# H1DR20.net
KiCad netlist of a schematic drawn in EAGLE
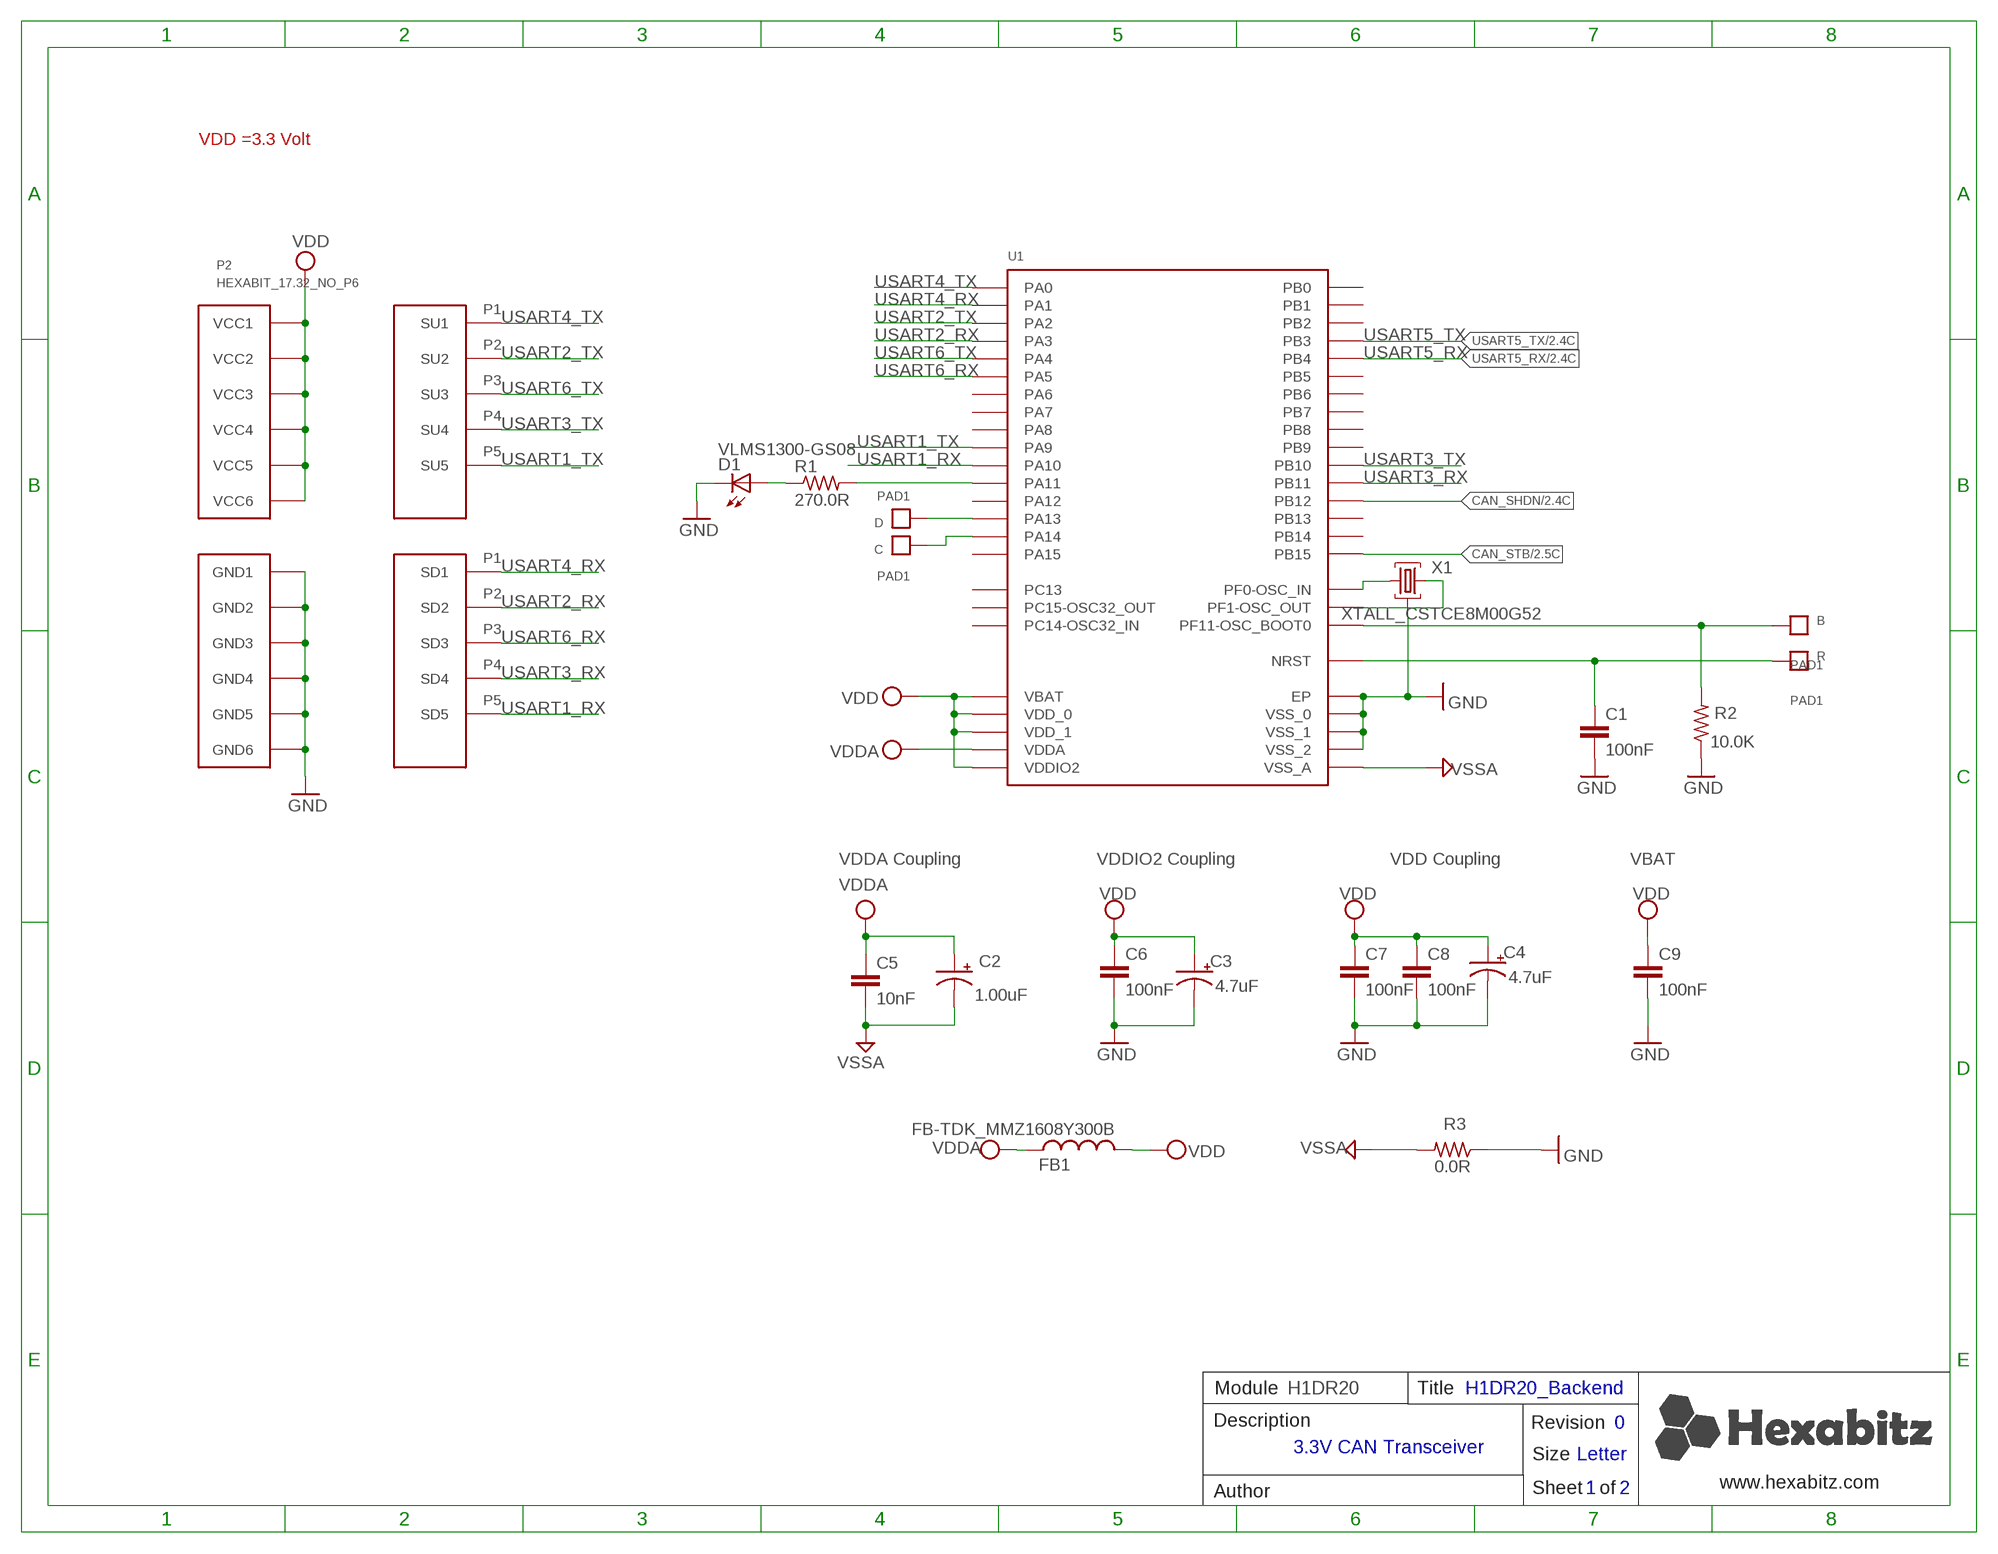
[diagram p0: schematic, sheet 1]
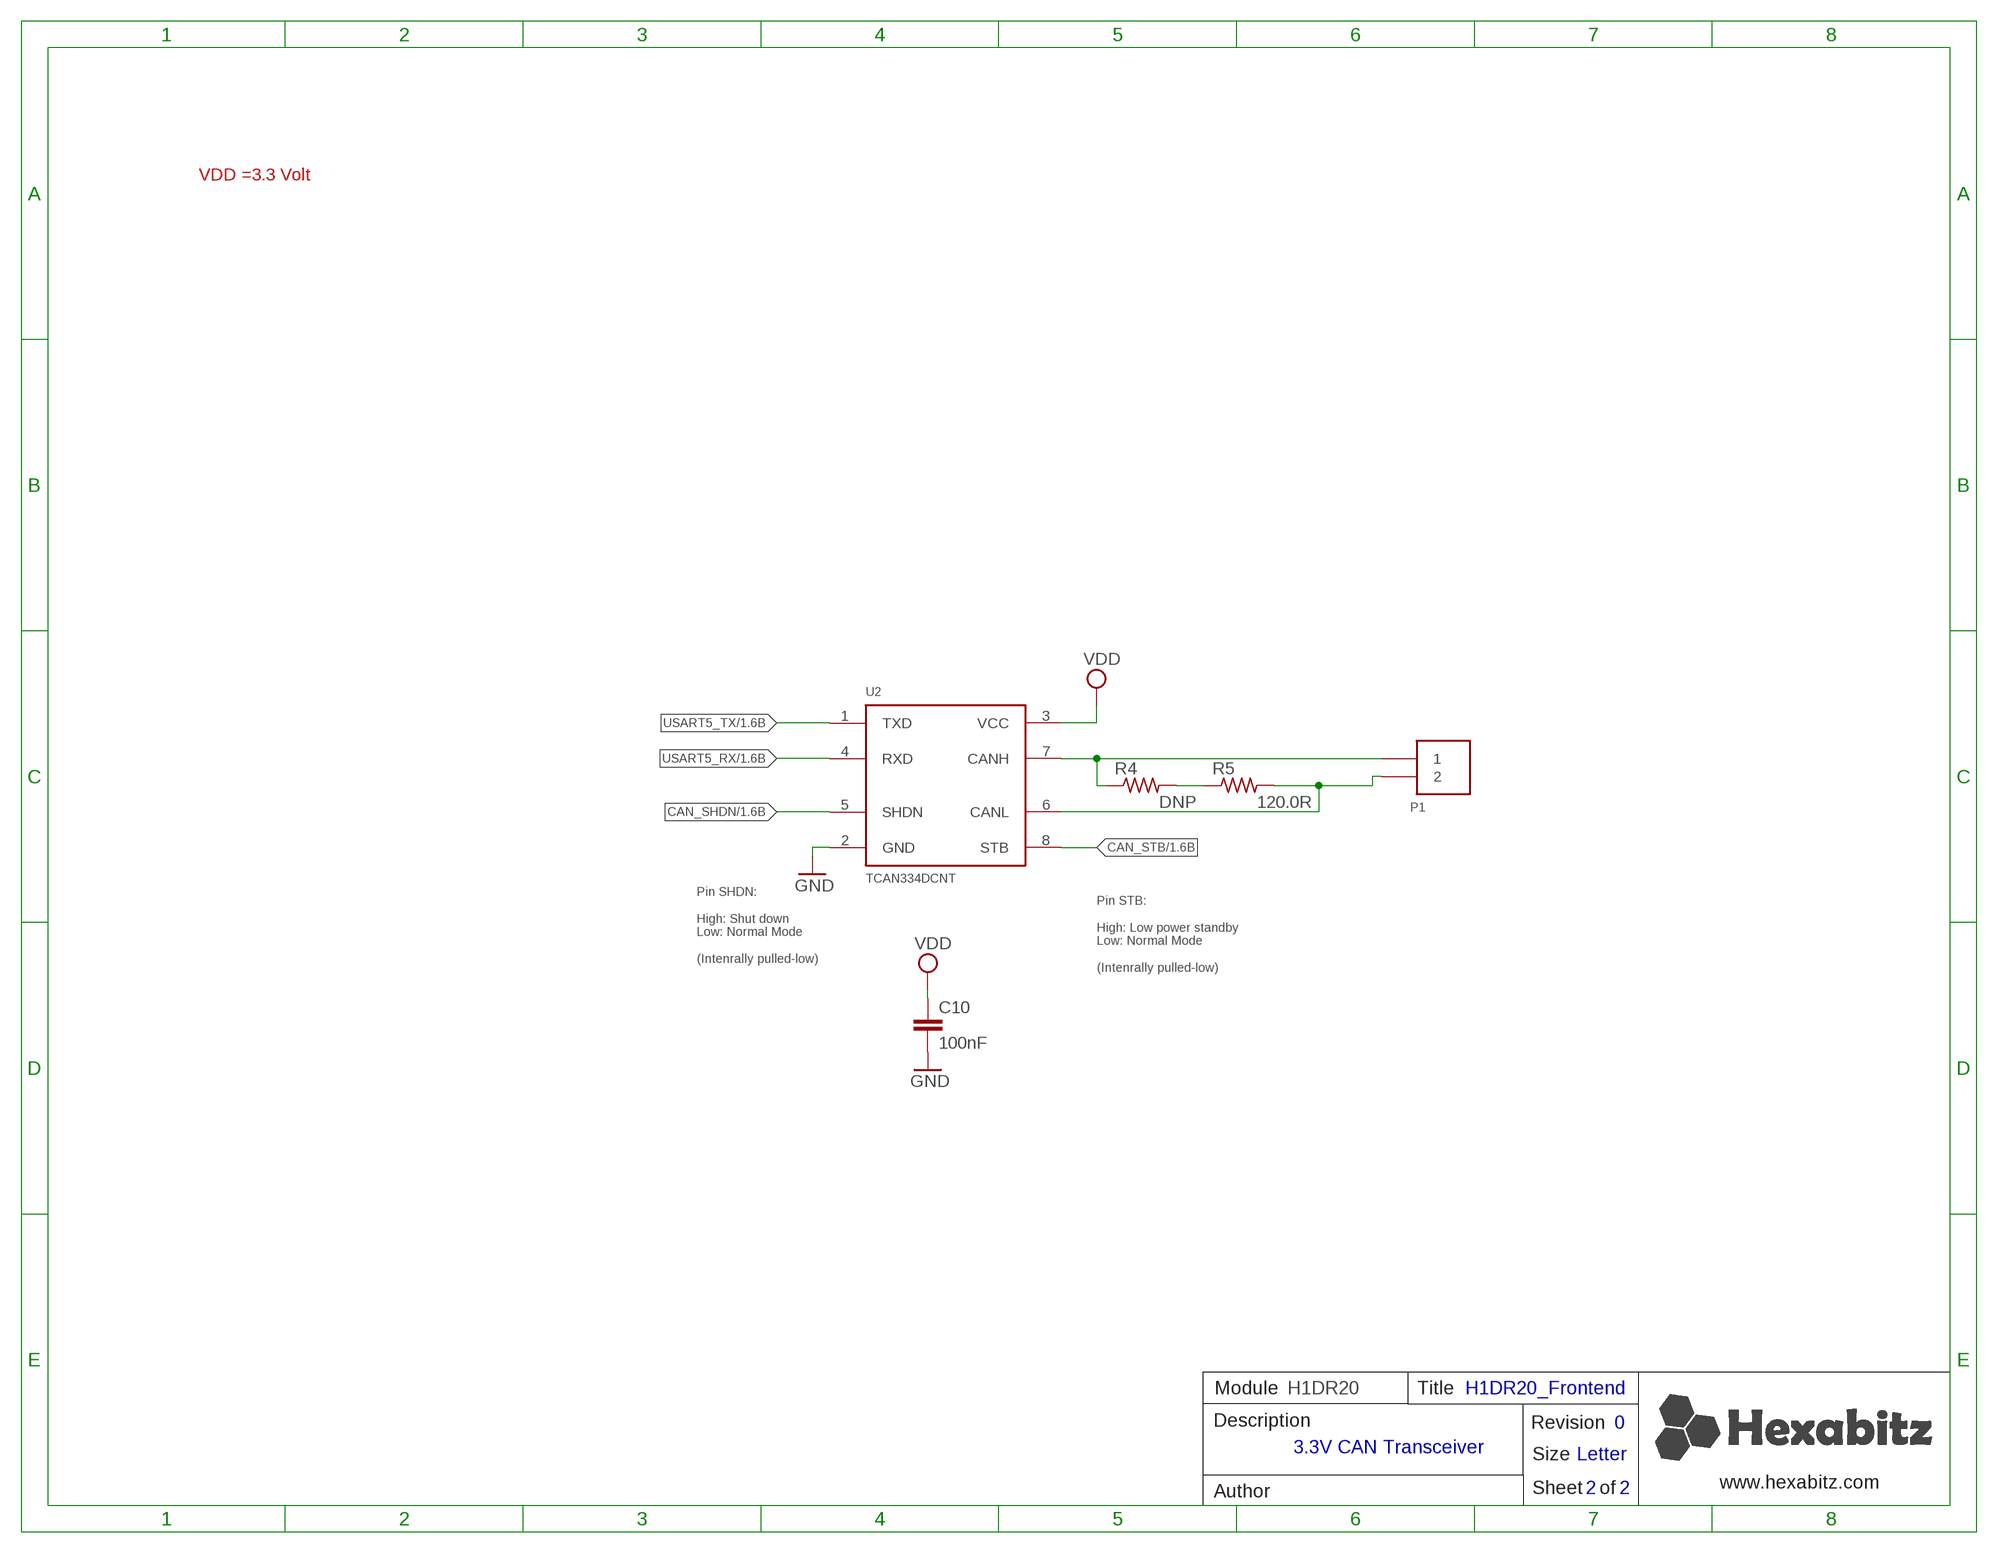
[diagram p1: schematic, sheet 2]

(export (version "E")
  (design (tool "Eeschema 10.0.6"))
  (components
    (comp (ref "B")
      (value "PAD1")
      (footprint "eagle-import:PAD1")
      (libsource (lib "eagle-import") (part "PAD1"))
    )
    (comp (ref "C")
      (value "PAD1")
      (footprint "eagle-import:PAD1")
      (libsource (lib "eagle-import") (part "PAD1"))
    )
    (comp (ref "C1")
      (value "100nF")
      (footprint "eagle-import:C-0603")
      (fields
        (field (name "CAPACITANCE") "100nF")
        (field (name "MFN") "KEMET")
        (field (name "MPN") "C0603C104K8RACTU")
        (field (name "OCTOPART_URL") "https://octopart.com/c0603c104k8ractu-kemet-145075?r=sp&s=9bS9ASSwSEqMCE9KBEQZ0g")
        (field (name "TOLERANCE") "10%")
        (field (name "VOLTAGE_RATING") "10V")
      )
      (libsource (lib "eagle-import") (part "C-0603"))
    )
    (comp (ref "C2")
      (value "1.00uF")
      (footprint "eagle-import:C-0805-POL")
      (fields
        (field (name "CAPACITANCE") "1.00uF")
        (field (name "MFN") "Yageo")
        (field (name "MPN") "CC0805KKX7R7BB105")
        (field (name "OCTOPART_URL") "https://octopart.com/cc0805kkx7r7bb105-yageo-8376555?r=sp&s=YKl1wwtkROau_X5nniH2ig")
        (field (name "TOLERANCE") "10%")
        (field (name "VOLTAGE_RATING") "16V")
      )
      (libsource (lib "eagle-import") (part "C-0805-POL"))
    )
    (comp (ref "C3")
      (value "4.7uF")
      (footprint "eagle-import:C-0805-POL")
      (fields
        (field (name "CAPACITANCE") "4.7uF")
        (field (name "MFN") "Murata")
        (field (name "MPN") "GRM21BC81E475KA12L")
        (field (name "OCTOPART_URL") "https://octopart.com/grm21bc81e475ka12l-murata-10331911?r=sp&s=RY3qZSD8T6mG6TC9CHI5qQ")
        (field (name "TOLERANCE") "10%")
        (field (name "VOLTAGE_RATING") "25V")
      )
      (libsource (lib "eagle-import") (part "C-0805-POL"))
    )
    (comp (ref "C4")
      (value "4.7uF")
      (footprint "eagle-import:C-0805-POL")
      (fields
        (field (name "CAPACITANCE") "4.7uF")
        (field (name "MFN") "Murata")
        (field (name "MPN") "GRM21BC81E475KA12L")
        (field (name "OCTOPART_URL") "https://octopart.com/grm21bc81e475ka12l-murata-10331911?r=sp&s=RY3qZSD8T6mG6TC9CHI5qQ")
        (field (name "TOLERANCE") "10%")
        (field (name "VOLTAGE_RATING") "25V")
      )
      (libsource (lib "eagle-import") (part "C-0805-POL"))
    )
    (comp (ref "C5")
      (value "10nF")
      (footprint "eagle-import:C-0603")
      (fields
        (field (name "CAPACITANCE") "10nF")
        (field (name "MFN") "KEMET")
        (field (name "MPN") "C0603C103K5RACTU")
        (field (name "OCTOPART_URL") "https://octopart.com/c0603c103k5ractu-kemet-133094?r=sp&s=R_iPBxLnSmGqhkU2rIMFpg")
        (field (name "TOLERANCE") "10%")
        (field (name "VOLTAGE_RATING") "50V")
      )
      (libsource (lib "eagle-import") (part "C-0603"))
    )
    (comp (ref "C6")
      (value "100nF")
      (footprint "eagle-import:C-0603")
      (fields
        (field (name "CAPACITANCE") "100nF")
        (field (name "MFN") "KEMET")
        (field (name "MPN") "C0603C104K8RACTU")
        (field (name "OCTOPART_URL") "https://octopart.com/c0603c104k8ractu-kemet-145075?r=sp&s=9bS9ASSwSEqMCE9KBEQZ0g")
        (field (name "TOLERANCE") "10%")
        (field (name "VOLTAGE_RATING") "10V")
      )
      (libsource (lib "eagle-import") (part "C-0603"))
    )
    (comp (ref "C7")
      (value "100nF")
      (footprint "eagle-import:C-0603")
      (fields
        (field (name "CAPACITANCE") "100nF")
        (field (name "MFN") "KEMET")
        (field (name "MPN") "C0603C104K8RACTU")
        (field (name "OCTOPART_URL") "https://octopart.com/c0603c104k8ractu-kemet-145075?r=sp&s=9bS9ASSwSEqMCE9KBEQZ0g")
        (field (name "TOLERANCE") "10%")
        (field (name "VOLTAGE_RATING") "10")
      )
      (libsource (lib "eagle-import") (part "C-0603"))
    )
    (comp (ref "C8")
      (value "100nF")
      (footprint "eagle-import:C-0603")
      (fields
        (field (name "CAPACITANCE") "100nF")
        (field (name "MFN") "KEMET")
        (field (name "MPN") "C0603C104K8RACTU")
        (field (name "OCTOPART_URL") "https://octopart.com/c0603c104k8ractu-kemet-145075?r=sp&s=9bS9ASSwSEqMCE9KBEQZ0g")
        (field (name "TOLERANCE") "10%")
        (field (name "VOLTAGE_RATING") "10V")
      )
      (libsource (lib "eagle-import") (part "C-0603"))
    )
    (comp (ref "C9")
      (value "100nF")
      (footprint "eagle-import:C-0603")
      (fields
        (field (name "CAPACITANCE") "100nF")
        (field (name "MFN") "KEMET")
        (field (name "MPN") "C0603C104K8RACTU")
        (field (name "OCTOPART_URL") "https://octopart.com/c0603c104k8ractu-kemet-145075?r=sp&s=9bS9ASSwSEqMCE9KBEQZ0g")
        (field (name "TOLERANCE") "10V")
        (field (name "VOLTAGE_RATING") "10%")
      )
      (libsource (lib "eagle-import") (part "C-0603"))
    )
    (comp (ref "D")
      (value "PAD1")
      (footprint "eagle-import:PAD1")
      (libsource (lib "eagle-import") (part "PAD1"))
    )
    (comp (ref "D1")
      (value "VLMS1300-GS08")
      (footprint "eagle-import:VLMS1300-GS08")
      (fields
        (field (name "MFN") "Vishay")
        (field (name "MPN") "VLMS1300-GS08")
        (field (name "OCTOPART_URL") "https://octopart.com/vlms1300-gs08-vishay-21709201?r=sp&s=_gcP4_q8T1SC6PJQPTQ9yA")
      )
      (libsource (lib "eagle-import") (part "VLMS1300-GS08"))
    )
    (comp (ref "FB1")
      (value "FB-TDK_MMZ1608Y300B")
      (footprint "eagle-import:FB-TDK_MMZ1608Y300B")
      (fields
        (field (name "MFN") "TDK ")
        (field (name "MPN") "MMZ1608Y300B")
        (field (name "OCTOPART_URL") "https://octopart.com/mmz1608y300b-tdk-368280?r=sp&s=cd9_2ZEqQ9q9UNBuQgHAiA")
      )
      (libsource (lib "eagle-import") (part "FB-TDK_MMZ1608Y300B"))
    )
    (comp (ref "P2")
      (value "HEXABIT_17.32_NO_P6")
      (footprint "eagle-import:HEXABIT_17.32_NO_P6")
      (libsource (lib "eagle-import") (part "HEXABIT_17.32_NO_P6"))
    )
    (comp (ref "R")
      (value "PAD1")
      (footprint "eagle-import:PAD1")
      (libsource (lib "eagle-import") (part "PAD1"))
    )
    (comp (ref "R1")
      (value "270.0R")
      (footprint "eagle-import:R-0603")
      (fields
        (field (name "MFN") "Yageo")
        (field (name "MPN") "RC0603FR-07270RL")
        (field (name "OCTOPART_URL") "https://octopart.com/search?q=RC0603FR-07270RL&start=0")
        (field (name "RESISTANCE") "270.0 Ohm")
        (field (name "TOLERANCE") "1%")
      )
      (libsource (lib "eagle-import") (part "R-0603"))
    )
    (comp (ref "R2")
      (value "10.0K")
      (footprint "eagle-import:R-0603")
      (fields
        (field (name "MFN") "Yageo")
        (field (name "MPN") "RC0603JR-0710KL")
        (field (name "OCTOPART_URL") "https://octopart.com/search?q=RC0603JR-0710KL&start=0")
        (field (name "RESISTANCE") "10.0K Ohm")
        (field (name "TOLERANCE") "5%")
      )
      (libsource (lib "eagle-import") (part "R-0603"))
    )
    (comp (ref "R3")
      (value "0.0R")
      (footprint "eagle-import:R-0603")
      (fields
        (field (name "MFN") "Yageo")
        (field (name "MPN") "RC0603JR-070RL")
        (field (name "OCTOPART_URL") "https://octopart.com/rc0603jr-070rl-yageo-1241539?r=sp&s=X2NteqRjRNWrnx42Y0aliA")
        (field (name "RESISTANCE") "0.0 Ohm")
      )
      (libsource (lib "eagle-import") (part "R-0603"))
    )
    (comp (ref "U1")
      (value "STM32F091CBU6")
      (footprint "eagle-import:STM32F091CBU6")
      (libsource (lib "eagle-import") (part "STM32F091CBU6"))
    )
    (comp (ref "X1")
      (value "XTALL_CSTCE8M00G52")
      (footprint "eagle-import:XTALL_CSTCE8M00G52")
      (fields (field (name "MPN") "CSTCE8M00G52Z-R0"))
      (libsource (lib "eagle-import") (part "XTALL_CSTCE8M00G52"))
    )
    (comp (ref "C10")
      (value "100nF")
      (footprint "eagle-import:C-0603")
      (fields
        (field (name "CAPACITANCE") "100nF")
        (field (name "MFN") "KEMET")
        (field (name "MPN") "C0603C104K8RACTU")
        (field (name "OCTOPART_URL") "https://octopart.com/c0603c104k8ractu-kemet-145075?r=sp&s=9bS9ASSwSEqMCE9KBEQZ0g")
        (field (name "TOLERANCE") "10%")
        (field (name "VOLTAGE_RATING") "10V")
      )
      (libsource (lib "eagle-import") (part "C-0603"))
    )
    (comp (ref "P1")
      (value "1546111-2")
      (footprint "eagle-import:1546111-2")
      (libsource (lib "eagle-import") (part "1546111-2"))
    )
    (comp (ref "R4")
      (value "DNP")
      (footprint "eagle-import:R-0603")
      (fields
        (field (name "MFN") "Yageo")
        (field (name "MPN") "RC0603JR-070RL")
        (field (name "OCTOPART_URL") "https://octopart.com/search?q=RC0603JR-070RL")
        (field (name "RESISTANCE") "0.0 Ohm")
      )
      (libsource (lib "eagle-import") (part "R-0603"))
    )
    (comp (ref "R5")
      (value "120.0R")
      (footprint "eagle-import:R-0603")
      (fields
        (field (name "MFN") "Yageo")
        (field (name "MPN") "AC0603FR-07120RL")
        (field (name "OCTOPART_URL") "https://octopart.com/search?q=AC0603FR-07120RL&start=0")
        (field (name "RESISTANCE") "120.0 Ohm")
        (field (name "TOLERANCE") "1%")
      )
      (libsource (lib "eagle-import") (part "R-0603"))
    )
    (comp (ref "U2")
      (value "TCAN334DCNT")
      (footprint "eagle-import:TCAN334DCNT")
      (libsource (lib "eagle-import") (part "TCAN334DCNT"))
    )
  )
  (nets
    (net (code "1") (name "CAN_SHDN") (class "Default")
      (node (ref "U1") (pin "P$25") (pinfunction "PB12_P$25") (pintype "bidirectional"))
      (node (ref "U2") (pin "5") (pinfunction "SHDN_5") (pintype "bidirectional"))
    )
    (net (code "2") (name "CAN_STB") (class "Default")
      (node (ref "U1") (pin "P$28") (pinfunction "PB15_P$28") (pintype "bidirectional"))
      (node (ref "U2") (pin "8") (pinfunction "STB_8") (pintype "bidirectional"))
    )
    (net (code "3") (name "GND") (class "Default")
      (node (ref "C1") (pin "2") (pinfunction "2_2") (pintype "passive"))
      (node (ref "C10") (pin "2") (pinfunction "2_2") (pintype "passive"))
      (node (ref "C3") (pin "2") (pinfunction "-_2") (pintype "passive"))
      (node (ref "C4") (pin "2") (pinfunction "-_2") (pintype "passive"))
      (node (ref "C6") (pin "2") (pinfunction "2_2") (pintype "passive"))
      (node (ref "C7") (pin "2") (pinfunction "2_2") (pintype "passive"))
      (node (ref "C8") (pin "2") (pinfunction "2_2") (pintype "passive"))
      (node (ref "C9") (pin "2") (pinfunction "2_2") (pintype "passive"))
      (node (ref "D1") (pin "C") (pinfunction "C_C") (pintype "passive"))
      (node (ref "P2") (pin "10") (pinfunction "GND4_10") (pintype "power_in"))
      (node (ref "P2") (pin "11") (pinfunction "GND5_11") (pintype "power_in"))
      (node (ref "P2") (pin "12") (pinfunction "GND6_12") (pintype "power_in"))
      (node (ref "P2") (pin "7") (pinfunction "GND1_7") (pintype "power_in"))
      (node (ref "P2") (pin "8") (pinfunction "GND2_8") (pintype "power_in"))
      (node (ref "P2") (pin "9") (pinfunction "GND3_9") (pintype "power_in"))
      (node (ref "R2") (pin "1") (pinfunction "1_1") (pintype "passive"))
      (node (ref "R3") (pin "1") (pinfunction "1_1") (pintype "passive"))
      (node (ref "U1") (pin "EP") (pinfunction "EP_EP") (pintype "power_in"))
      (node (ref "U1") (pin "P$23") (pinfunction "VSS_0_P$23") (pintype "power_in"))
      (node (ref "U1") (pin "P$35") (pinfunction "VSS_1_P$35") (pintype "power_in"))
      (node (ref "U1") (pin "P$47") (pinfunction "VSS_2_P$47") (pintype "power_in"))
      (node (ref "U2") (pin "2") (pinfunction "GND_2") (pintype "bidirectional"))
      (node (ref "X1") (pin "P$2") (pinfunction "2_P$2") (pintype "passive"))
    )
    (net (code "4") (name "Net-(D1-PadA)") (class "Default")
      (node (ref "D1") (pin "A") (pinfunction "A_A") (pintype "passive"))
      (node (ref "R1") (pin "1") (pinfunction "1_1") (pintype "passive"))
    )
    (net (code "5") (name "Net-(R4-Pad2)") (class "Default")
      (node (ref "R4") (pin "2") (pinfunction "2_2") (pintype "passive"))
      (node (ref "R5") (pin "1") (pinfunction "1_1") (pintype "passive"))
    )
    (net (code "6") (name "Net-(U1-NRST)") (class "Default")
      (node (ref "C1") (pin "1") (pinfunction "1_1") (pintype "passive"))
      (node (ref "R") (pin "P$1") (pinfunction "P$1_P$1") (pintype "passive"))
      (node (ref "R") (pin "P$2") (pinfunction "P$1_P$2") (pintype "passive"))
      (node (ref "U1") (pin "P$7") (pinfunction "NRST_P$7") (pintype "passive"))
    )
    (net (code "7") (name "Net-(U1-PA11)") (class "Default")
      (node (ref "R1") (pin "2") (pinfunction "2_2") (pintype "passive"))
      (node (ref "U1") (pin "P$32") (pinfunction "PA11_P$32") (pintype "bidirectional"))
    )
    (net (code "8") (name "Net-(U1-PA13)") (class "Default")
      (node (ref "D") (pin "P$1") (pinfunction "P$1_P$1") (pintype "passive"))
      (node (ref "D") (pin "P$2") (pinfunction "P$1_P$2") (pintype "passive"))
      (node (ref "U1") (pin "P$34") (pinfunction "PA13_P$34") (pintype "bidirectional"))
    )
    (net (code "9") (name "Net-(U1-PA14)") (class "Default")
      (node (ref "C") (pin "P$1") (pinfunction "P$1_P$1") (pintype "passive"))
      (node (ref "C") (pin "P$2") (pinfunction "P$1_P$2") (pintype "passive"))
      (node (ref "U1") (pin "P$37") (pinfunction "PA14_P$37") (pintype "bidirectional"))
    )
    (net (code "10") (name "Net-(U1-PF0-OSC_IN)") (class "Default")
      (node (ref "U1") (pin "P$5") (pinfunction "PF0-OSC_IN_P$5") (pintype "bidirectional"))
      (node (ref "X1") (pin "P$1") (pinfunction "1_P$1") (pintype "passive"))
    )
    (net (code "11") (name "Net-(U1-PF1-OSC_OUT)") (class "Default")
      (node (ref "U1") (pin "P$6") (pinfunction "PF1-OSC_OUT_P$6") (pintype "bidirectional"))
      (node (ref "X1") (pin "P$3") (pinfunction "3_P$3") (pintype "passive"))
    )
    (net (code "12") (name "Net-(U1-PF11-OSC_BOOT0)") (class "Default")
      (node (ref "B") (pin "P$1") (pinfunction "P$1_P$1") (pintype "passive"))
      (node (ref "B") (pin "P$2") (pinfunction "P$1_P$2") (pintype "passive"))
      (node (ref "R2") (pin "2") (pinfunction "2_2") (pintype "passive"))
      (node (ref "U1") (pin "P$44") (pinfunction "PF11-OSC_BOOT0_P$44") (pintype "bidirectional"))
    )
    (net (code "13") (name "Net-(U2-CANH)") (class "Default")
      (node (ref "P1") (pin "1") (pinfunction "1_1") (pintype "power_in"))
      (node (ref "R4") (pin "1") (pinfunction "1_1") (pintype "passive"))
      (node (ref "U2") (pin "7") (pinfunction "CANH_7") (pintype "bidirectional"))
    )
    (net (code "14") (name "Net-(U2-CANL)") (class "Default")
      (node (ref "P1") (pin "2") (pinfunction "2_2") (pintype "power_in"))
      (node (ref "R5") (pin "2") (pinfunction "2_2") (pintype "passive"))
      (node (ref "U2") (pin "6") (pinfunction "CANL_6") (pintype "bidirectional"))
    )
    (net (code "15") (name "USART1_RX") (class "Default")
      (node (ref "P2") (pin "23") (pinfunction "SD5_23") (pintype "bidirectional"))
      (node (ref "U1") (pin "P$31") (pinfunction "PA10_P$31") (pintype "bidirectional"))
    )
    (net (code "16") (name "USART1_TX") (class "Default")
      (node (ref "P2") (pin "17") (pinfunction "SU5_17") (pintype "bidirectional"))
      (node (ref "U1") (pin "P$30") (pinfunction "PA9_P$30") (pintype "bidirectional"))
    )
    (net (code "17") (name "USART2_RX") (class "Default")
      (node (ref "P2") (pin "20") (pinfunction "SD2_20") (pintype "bidirectional"))
      (node (ref "U1") (pin "P$13") (pinfunction "PA3_P$13") (pintype "bidirectional"))
    )
    (net (code "18") (name "USART2_TX") (class "Default")
      (node (ref "P2") (pin "14") (pinfunction "SU2_14") (pintype "bidirectional"))
      (node (ref "U1") (pin "P$12") (pinfunction "PA2_P$12") (pintype "bidirectional"))
    )
    (net (code "19") (name "USART3_RX") (class "Default")
      (node (ref "P2") (pin "22") (pinfunction "SD4_22") (pintype "bidirectional"))
      (node (ref "U1") (pin "P$22") (pinfunction "PB11_P$22") (pintype "bidirectional"))
    )
    (net (code "20") (name "USART3_TX") (class "Default")
      (node (ref "P2") (pin "16") (pinfunction "SU4_16") (pintype "bidirectional"))
      (node (ref "U1") (pin "P$21") (pinfunction "PB10_P$21") (pintype "bidirectional"))
    )
    (net (code "21") (name "USART4_RX") (class "Default")
      (node (ref "P2") (pin "19") (pinfunction "SD1_19") (pintype "bidirectional"))
      (node (ref "U1") (pin "P$11") (pinfunction "PA1_P$11") (pintype "bidirectional"))
    )
    (net (code "22") (name "USART4_TX") (class "Default")
      (node (ref "P2") (pin "13") (pinfunction "SU1_13") (pintype "bidirectional"))
      (node (ref "U1") (pin "P$10") (pinfunction "PA0_P$10") (pintype "bidirectional"))
    )
    (net (code "23") (name "USART5_RX") (class "Default")
      (node (ref "U1") (pin "P$40") (pinfunction "PB4_P$40") (pintype "bidirectional"))
      (node (ref "U2") (pin "4") (pinfunction "RXD_4") (pintype "bidirectional"))
    )
    (net (code "24") (name "USART5_TX") (class "Default")
      (node (ref "U1") (pin "P$39") (pinfunction "PB3_P$39") (pintype "bidirectional"))
      (node (ref "U2") (pin "1") (pinfunction "TXD_1") (pintype "bidirectional"))
    )
    (net (code "25") (name "USART6_RX") (class "Default")
      (node (ref "P2") (pin "21") (pinfunction "SD3_21") (pintype "bidirectional"))
      (node (ref "U1") (pin "P$15") (pinfunction "PA5_P$15") (pintype "bidirectional"))
    )
    (net (code "26") (name "USART6_TX") (class "Default")
      (node (ref "P2") (pin "15") (pinfunction "SU3_15") (pintype "bidirectional"))
      (node (ref "U1") (pin "P$14") (pinfunction "PA4_P$14") (pintype "bidirectional"))
    )
    (net (code "27") (name "VDD") (class "Default")
      (node (ref "C10") (pin "1") (pinfunction "1_1") (pintype "passive"))
      (node (ref "C3") (pin "1") (pinfunction "+_1") (pintype "passive"))
      (node (ref "C4") (pin "1") (pinfunction "+_1") (pintype "passive"))
      (node (ref "C6") (pin "1") (pinfunction "1_1") (pintype "passive"))
      (node (ref "C7") (pin "1") (pinfunction "1_1") (pintype "passive"))
      (node (ref "C8") (pin "1") (pinfunction "1_1") (pintype "passive"))
      (node (ref "C9") (pin "1") (pinfunction "1_1") (pintype "passive"))
      (node (ref "FB1") (pin "2") (pinfunction "2_2") (pintype "passive"))
      (node (ref "P2") (pin "1") (pinfunction "VCC1_1") (pintype "power_in"))
      (node (ref "P2") (pin "2") (pinfunction "VCC2_2") (pintype "power_in"))
      (node (ref "P2") (pin "3") (pinfunction "VCC3_3") (pintype "power_in"))
      (node (ref "P2") (pin "4") (pinfunction "VCC4_4") (pintype "power_in"))
      (node (ref "P2") (pin "5") (pinfunction "VCC5_5") (pintype "power_in"))
      (node (ref "P2") (pin "6") (pinfunction "VCC6_6") (pintype "power_in"))
      (node (ref "U1") (pin "P$1") (pinfunction "VBAT_P$1") (pintype "power_in"))
      (node (ref "U1") (pin "P$24") (pinfunction "VDD_0_P$24") (pintype "power_in"))
      (node (ref "U1") (pin "P$36") (pinfunction "VDDIO2_P$36") (pintype "power_in"))
      (node (ref "U1") (pin "P$48") (pinfunction "VDD_1_P$48") (pintype "power_in"))
      (node (ref "U2") (pin "3") (pinfunction "VCC_3") (pintype "bidirectional"))
    )
    (net (code "28") (name "VDDA") (class "Default")
      (node (ref "C2") (pin "1") (pinfunction "+_1") (pintype "passive"))
      (node (ref "C5") (pin "1") (pinfunction "1_1") (pintype "passive"))
      (node (ref "FB1") (pin "1") (pinfunction "1_1") (pintype "passive"))
      (node (ref "U1") (pin "P$9") (pinfunction "VDDA_P$9") (pintype "power_in"))
    )
    (net (code "29") (name "VSSA") (class "Default")
      (node (ref "C2") (pin "2") (pinfunction "-_2") (pintype "passive"))
      (node (ref "C5") (pin "2") (pinfunction "2_2") (pintype "passive"))
      (node (ref "R3") (pin "2") (pinfunction "2_2") (pintype "passive"))
      (node (ref "U1") (pin "P$8") (pinfunction "VSS_A_P$8") (pintype "power_in"))
    )
    (net (code "30") (name "unconnected-(U1-PA6-PadP$16)") (class "Default")
      (node (ref "U1") (pin "P$16") (pinfunction "PA6_P$16") (pintype "bidirectional"))
    )
    (net (code "31") (name "unconnected-(U1-PA7-PadP$17)") (class "Default")
      (node (ref "U1") (pin "P$17") (pinfunction "PA7_P$17") (pintype "bidirectional"))
    )
    (net (code "32") (name "unconnected-(U1-PA8-PadP$29)") (class "Default")
      (node (ref "U1") (pin "P$29") (pinfunction "PA8_P$29") (pintype "bidirectional"))
    )
    (net (code "33") (name "unconnected-(U1-PA12-PadP$33)") (class "Default")
      (node (ref "U1") (pin "P$33") (pinfunction "PA12_P$33") (pintype "bidirectional"))
    )
    (net (code "34") (name "unconnected-(U1-PA15-PadP$38)") (class "Default")
      (node (ref "U1") (pin "P$38") (pinfunction "PA15_P$38") (pintype "bidirectional"))
    )
    (net (code "35") (name "unconnected-(U1-PB0-PadP$18)") (class "Default")
      (node (ref "U1") (pin "P$18") (pinfunction "PB0_P$18") (pintype "bidirectional"))
    )
    (net (code "36") (name "unconnected-(U1-PB1-PadP$19)") (class "Default")
      (node (ref "U1") (pin "P$19") (pinfunction "PB1_P$19") (pintype "bidirectional"))
    )
    (net (code "37") (name "unconnected-(U1-PB2-PadP$20)") (class "Default")
      (node (ref "U1") (pin "P$20") (pinfunction "PB2_P$20") (pintype "bidirectional"))
    )
    (net (code "38") (name "unconnected-(U1-PB5-PadP$41)") (class "Default")
      (node (ref "U1") (pin "P$41") (pinfunction "PB5_P$41") (pintype "bidirectional"))
    )
    (net (code "39") (name "unconnected-(U1-PB6-PadP$42)") (class "Default")
      (node (ref "U1") (pin "P$42") (pinfunction "PB6_P$42") (pintype "bidirectional"))
    )
    (net (code "40") (name "unconnected-(U1-PB7-PadP$43)") (class "Default")
      (node (ref "U1") (pin "P$43") (pinfunction "PB7_P$43") (pintype "bidirectional"))
    )
    (net (code "41") (name "unconnected-(U1-PB8-PadP$45)") (class "Default")
      (node (ref "U1") (pin "P$45") (pinfunction "PB8_P$45") (pintype "bidirectional"))
    )
    (net (code "42") (name "unconnected-(U1-PB9-PadP$46)") (class "Default")
      (node (ref "U1") (pin "P$46") (pinfunction "PB9_P$46") (pintype "bidirectional"))
    )
    (net (code "43") (name "unconnected-(U1-PB13-PadP$26)") (class "Default")
      (node (ref "U1") (pin "P$26") (pinfunction "PB13_P$26") (pintype "bidirectional"))
    )
    (net (code "44") (name "unconnected-(U1-PB14-PadP$27)") (class "Default")
      (node (ref "U1") (pin "P$27") (pinfunction "PB14_P$27") (pintype "bidirectional"))
    )
    (net (code "45") (name "unconnected-(U1-PC13-PadP$2)") (class "Default")
      (node (ref "U1") (pin "P$2") (pinfunction "PC13_P$2") (pintype "bidirectional"))
    )
    (net (code "46") (name "unconnected-(U1-PC14-OSC32_IN-PadP$3)") (class "Default")
      (node (ref "U1") (pin "P$3") (pinfunction "PC14-OSC32_IN_P$3") (pintype "bidirectional"))
    )
    (net (code "47") (name "unconnected-(U1-PC15-OSC32_OUT-PadP$4)") (class "Default")
      (node (ref "U1") (pin "P$4") (pinfunction "PC15-OSC32_OUT_P$4") (pintype "bidirectional"))
    )
  )
)
